# Sensors.net
KiCad netlist of a schematic drawn in Altium Designer
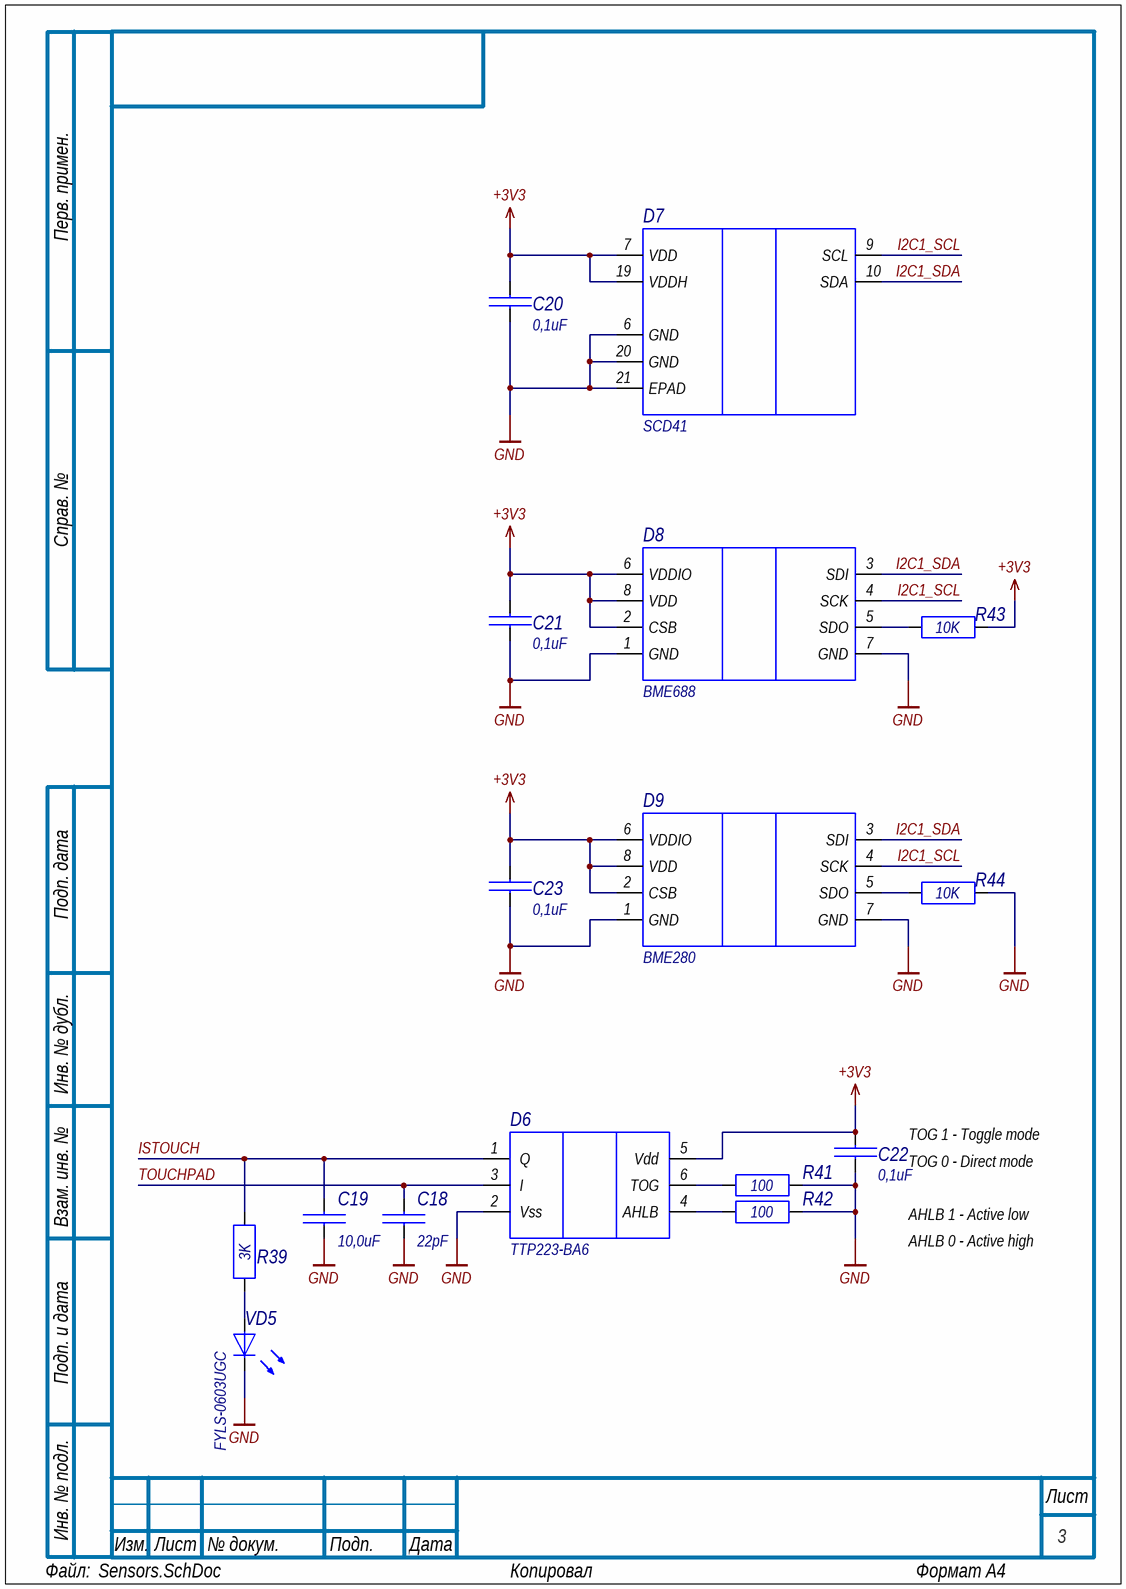
[diagram p0: Sensors.SchDoc]

(export (version "E")
  (design (tool "Eeschema 10.0.6"))
  (components
    (comp (ref "C18")
      (value "22pF")
      (footprint "CAP_0603")
      (description "Ceramic Capacitor SMD_0603 C0G")
      (fields (field (name "VOLTAGE") "50V") (field (name "PART NUMBER") "CAP_CER_0603_220_50_5_C0G"))
      (libsource (lib "myLib_ESKD") (part "CAPACITOR"))
    )
    (comp (ref "C19")
      (value "10,0uF")
      (footprint "CAP_0603")
      (description "Ceramic Capacitor SMD_0603 X5R")
      (fields (field (name "VOLTAGE") "25V") (field (name "PART NUMBER") "CAP_CER_0603_106_25_10_X5R"))
      (libsource (lib "myLib_ESKD") (part "CAPACITOR"))
    )
    (comp (ref "C20")
      (value "0,1uF")
      (footprint "CAP_0603")
      (description "Ceramic Capacitor SMD_0603 X7R")
      (fields (field (name "VOLTAGE") "25V") (field (name "PART NUMBER") "CAP_CER_0603_104_25_10_X7R"))
      (libsource (lib "myLib_ESKD") (part "CAPACITOR"))
    )
    (comp (ref "C21")
      (value "0,1uF")
      (footprint "CAP_0603")
      (description "Ceramic Capacitor SMD_0603 X7R")
      (fields (field (name "VOLTAGE") "25V") (field (name "PART NUMBER") "CAP_CER_0603_104_25_10_X7R"))
      (libsource (lib "myLib_ESKD") (part "CAPACITOR"))
    )
    (comp (ref "C22")
      (value "0,1uF")
      (footprint "CAP_0603")
      (description "Ceramic Capacitor SMD_0603 X7R")
      (fields (field (name "VOLTAGE") "25V") (field (name "PART NUMBER") "CAP_CER_0603_104_25_10_X7R"))
      (libsource (lib "myLib_ESKD") (part "CAPACITOR"))
    )
    (comp (ref "C23")
      (value "0,1uF")
      (footprint "CAP_0603")
      (description "Ceramic Capacitor SMD_0603 X7R")
      (fields (field (name "VOLTAGE") "25V") (field (name "PART NUMBER") "CAP_CER_0603_104_25_10_X7R"))
      (libsource (lib "myLib_ESKD") (part "CAPACITOR"))
    )
    (comp (ref "D6")
      (value "TTP223-BA6")
      (footprint "SOT-23-6L_1")
      (description "A touch pad detector")
      (fields (field (name "MANUFACTURER") "Tontek"))
      (libsource (lib "myLib_ESKD") (part "TTP223-BA6"))
    )
    (comp (ref "D7") (value "SCD41") (footprint "SCD41") (libsource (lib "myLib_ESKD") (part "SCD41")))
    (comp (ref "D8")
      (value "BME688")
      (footprint "BME688")
      (fields (field (name "Comment") "BME_SENSOR"))
      (libsource (lib "myLib_ESKD") (part "BME_SENSOR"))
    )
    (comp (ref "D9")
      (value "BME280")
      (footprint "BME280")
      (fields (field (name "Comment") "BME_SENSOR"))
      (libsource (lib "myLib_ESKD") (part "BME_SENSOR"))
    )
    (comp (ref "R39")
      (value "3K")
      (footprint "RES_0603")
      (description "Resistor fixed SMD_0603 5%")
      (fields (field (name "POWER") "100mW") (field (name "PART NUMBER") "RES_SMD_0603_3K_5%"))
      (libsource (lib "myLib_ESKD") (part "RESISTOR"))
    )
    (comp (ref "R41")
      (value "100")
      (footprint "RES_0603")
      (description "Resistor fixed SMD_0603 5%")
      (fields (field (name "POWER") "100mW") (field (name "PART NUMBER") "RES_SMD_0603_100R_5%"))
      (libsource (lib "myLib_ESKD") (part "RESISTOR"))
    )
    (comp (ref "R42")
      (value "100")
      (footprint "RES_0603")
      (description "Resistor fixed SMD_0603 5%")
      (fields (field (name "POWER") "100mW") (field (name "PART NUMBER") "RES_SMD_0603_100R_5%"))
      (libsource (lib "myLib_ESKD") (part "RESISTOR"))
    )
    (comp (ref "R43")
      (value "10K")
      (footprint "RES_0603")
      (description "Resistor fixed SMD_0603 5%")
      (fields (field (name "POWER") "100mW") (field (name "PART NUMBER") "RES_SMD_0603_10K_5%"))
      (libsource (lib "myLib_ESKD") (part "RESISTOR"))
    )
    (comp (ref "R44")
      (value "10K")
      (footprint "RES_0603")
      (description "Resistor fixed SMD_0603 5%")
      (fields (field (name "POWER") "100mW") (field (name "PART NUMBER") "RES_SMD_0603_10K_5%"))
      (libsource (lib "myLib_ESKD") (part "RESISTOR"))
    )
    (comp (ref "VD5")
      (value "FYLS-0603UGC")
      (footprint "LED_0603_G")
      (description "SMD 0603 LED Green")
      (fields (field (name "MANUFACTURER") "Foryard") (field (name "Comment") "LED"))
      (libsource (lib "myLib_ESKD") (part "LED"))
    )
  )
  (nets
    (net (code "1") (name "+3V3") (class "Default")
      (node (ref "C20") (pin "1") (pinfunction "1_1") (pintype "passive"))
      (node (ref "C21") (pin "1") (pinfunction "1_1") (pintype "passive"))
      (node (ref "C22") (pin "1") (pinfunction "1_1") (pintype "passive"))
      (node (ref "C23") (pin "1") (pinfunction "1_1") (pintype "passive"))
      (node (ref "D6") (pin "5") (pinfunction "Vdd_5") (pintype "passive"))
      (node (ref "D7") (pin "19") (pinfunction "VDDH_19") (pintype "passive"))
      (node (ref "D7") (pin "7") (pinfunction "VDD_7") (pintype "passive"))
      (node (ref "D8") (pin "2") (pinfunction "CSB_2") (pintype "passive"))
      (node (ref "D8") (pin "6") (pinfunction "VDDIO_6") (pintype "passive"))
      (node (ref "D8") (pin "8") (pinfunction "VDD_8") (pintype "passive"))
      (node (ref "D9") (pin "2") (pinfunction "CSB_2") (pintype "passive"))
      (node (ref "D9") (pin "6") (pinfunction "VDDIO_6") (pintype "passive"))
      (node (ref "D9") (pin "8") (pinfunction "VDD_8") (pintype "passive"))
      (node (ref "R43") (pin "2") (pinfunction "2_2") (pintype "passive"))
    )
    (net (code "2") (name "/I2C1_SCL") (class "Default")
      (node (ref "D7") (pin "9") (pinfunction "SCL_9") (pintype "passive"))
      (node (ref "D8") (pin "4") (pinfunction "SCK_4") (pintype "passive"))
      (node (ref "D9") (pin "4") (pinfunction "SCK_4") (pintype "passive"))
    )
    (net (code "3") (name "/I2C1_SDA") (class "Default")
      (node (ref "D7") (pin "10") (pinfunction "SDA_10") (pintype "passive"))
      (node (ref "D8") (pin "3") (pinfunction "SDI_3") (pintype "passive"))
      (node (ref "D9") (pin "3") (pinfunction "SDI_3") (pintype "passive"))
    )
    (net (code "4") (name "/ISTOUCH") (class "Default")
      (node (ref "C19") (pin "1") (pinfunction "1_1") (pintype "passive"))
      (node (ref "D6") (pin "1") (pinfunction "Q_1") (pintype "passive"))
      (node (ref "R39") (pin "2") (pinfunction "2_2") (pintype "passive"))
    )
    (net (code "5") (name "/TOUCHPAD") (class "Default")
      (node (ref "C18") (pin "2") (pinfunction "2_2") (pintype "passive"))
      (node (ref "D6") (pin "3") (pinfunction "I_3") (pintype "passive"))
    )
    (net (code "6") (name "GND") (class "Default")
      (node (ref "C18") (pin "1") (pinfunction "1_1") (pintype "passive"))
      (node (ref "C19") (pin "2") (pinfunction "2_2") (pintype "passive"))
      (node (ref "C20") (pin "2") (pinfunction "2_2") (pintype "passive"))
      (node (ref "C21") (pin "2") (pinfunction "2_2") (pintype "passive"))
      (node (ref "C22") (pin "2") (pinfunction "2_2") (pintype "passive"))
      (node (ref "C23") (pin "2") (pinfunction "2_2") (pintype "passive"))
      (node (ref "D6") (pin "2") (pinfunction "Vss_2") (pintype "passive"))
      (node (ref "D7") (pin "20") (pinfunction "GND_20") (pintype "passive"))
      (node (ref "D7") (pin "21") (pinfunction "EPAD_21") (pintype "passive"))
      (node (ref "D7") (pin "6") (pinfunction "GND_6") (pintype "passive"))
      (node (ref "D8") (pin "1") (pinfunction "GND_1") (pintype "passive"))
      (node (ref "D8") (pin "7") (pinfunction "GND_7") (pintype "passive"))
      (node (ref "D9") (pin "1") (pinfunction "GND_1") (pintype "passive"))
      (node (ref "D9") (pin "7") (pinfunction "GND_7") (pintype "passive"))
      (node (ref "R41") (pin "2") (pinfunction "2_2") (pintype "passive"))
      (node (ref "R42") (pin "2") (pinfunction "2_2") (pintype "passive"))
      (node (ref "R44") (pin "2") (pinfunction "2_2") (pintype "passive"))
      (node (ref "VD5") (pin "K") (pinfunction "K_K") (pintype "passive"))
    )
    (net (code "7") (name "Net-(D6-AHLB)") (class "Default")
      (node (ref "D6") (pin "4") (pinfunction "AHLB_4") (pintype "passive"))
      (node (ref "R42") (pin "1") (pinfunction "1_1") (pintype "passive"))
    )
    (net (code "8") (name "Net-(D6-TOG)") (class "Default")
      (node (ref "D6") (pin "6") (pinfunction "TOG_6") (pintype "passive"))
      (node (ref "R41") (pin "1") (pinfunction "1_1") (pintype "passive"))
    )
    (net (code "9") (name "Net-(D8-SDO)") (class "Default")
      (node (ref "D8") (pin "5") (pinfunction "SDO_5") (pintype "passive"))
      (node (ref "R43") (pin "1") (pinfunction "1_1") (pintype "passive"))
    )
    (net (code "10") (name "Net-(D9-SDO)") (class "Default")
      (node (ref "D9") (pin "5") (pinfunction "SDO_5") (pintype "passive"))
      (node (ref "R44") (pin "1") (pinfunction "1_1") (pintype "passive"))
    )
    (net (code "11") (name "Net-(R39-Pad1)") (class "Default")
      (node (ref "R39") (pin "1") (pinfunction "1_1") (pintype "passive"))
      (node (ref "VD5") (pin "A") (pinfunction "A_A") (pintype "passive"))
    )
  )
)
